# SBH_Charger_Main.net
KiCad netlist of a schematic drawn in Altium Designer
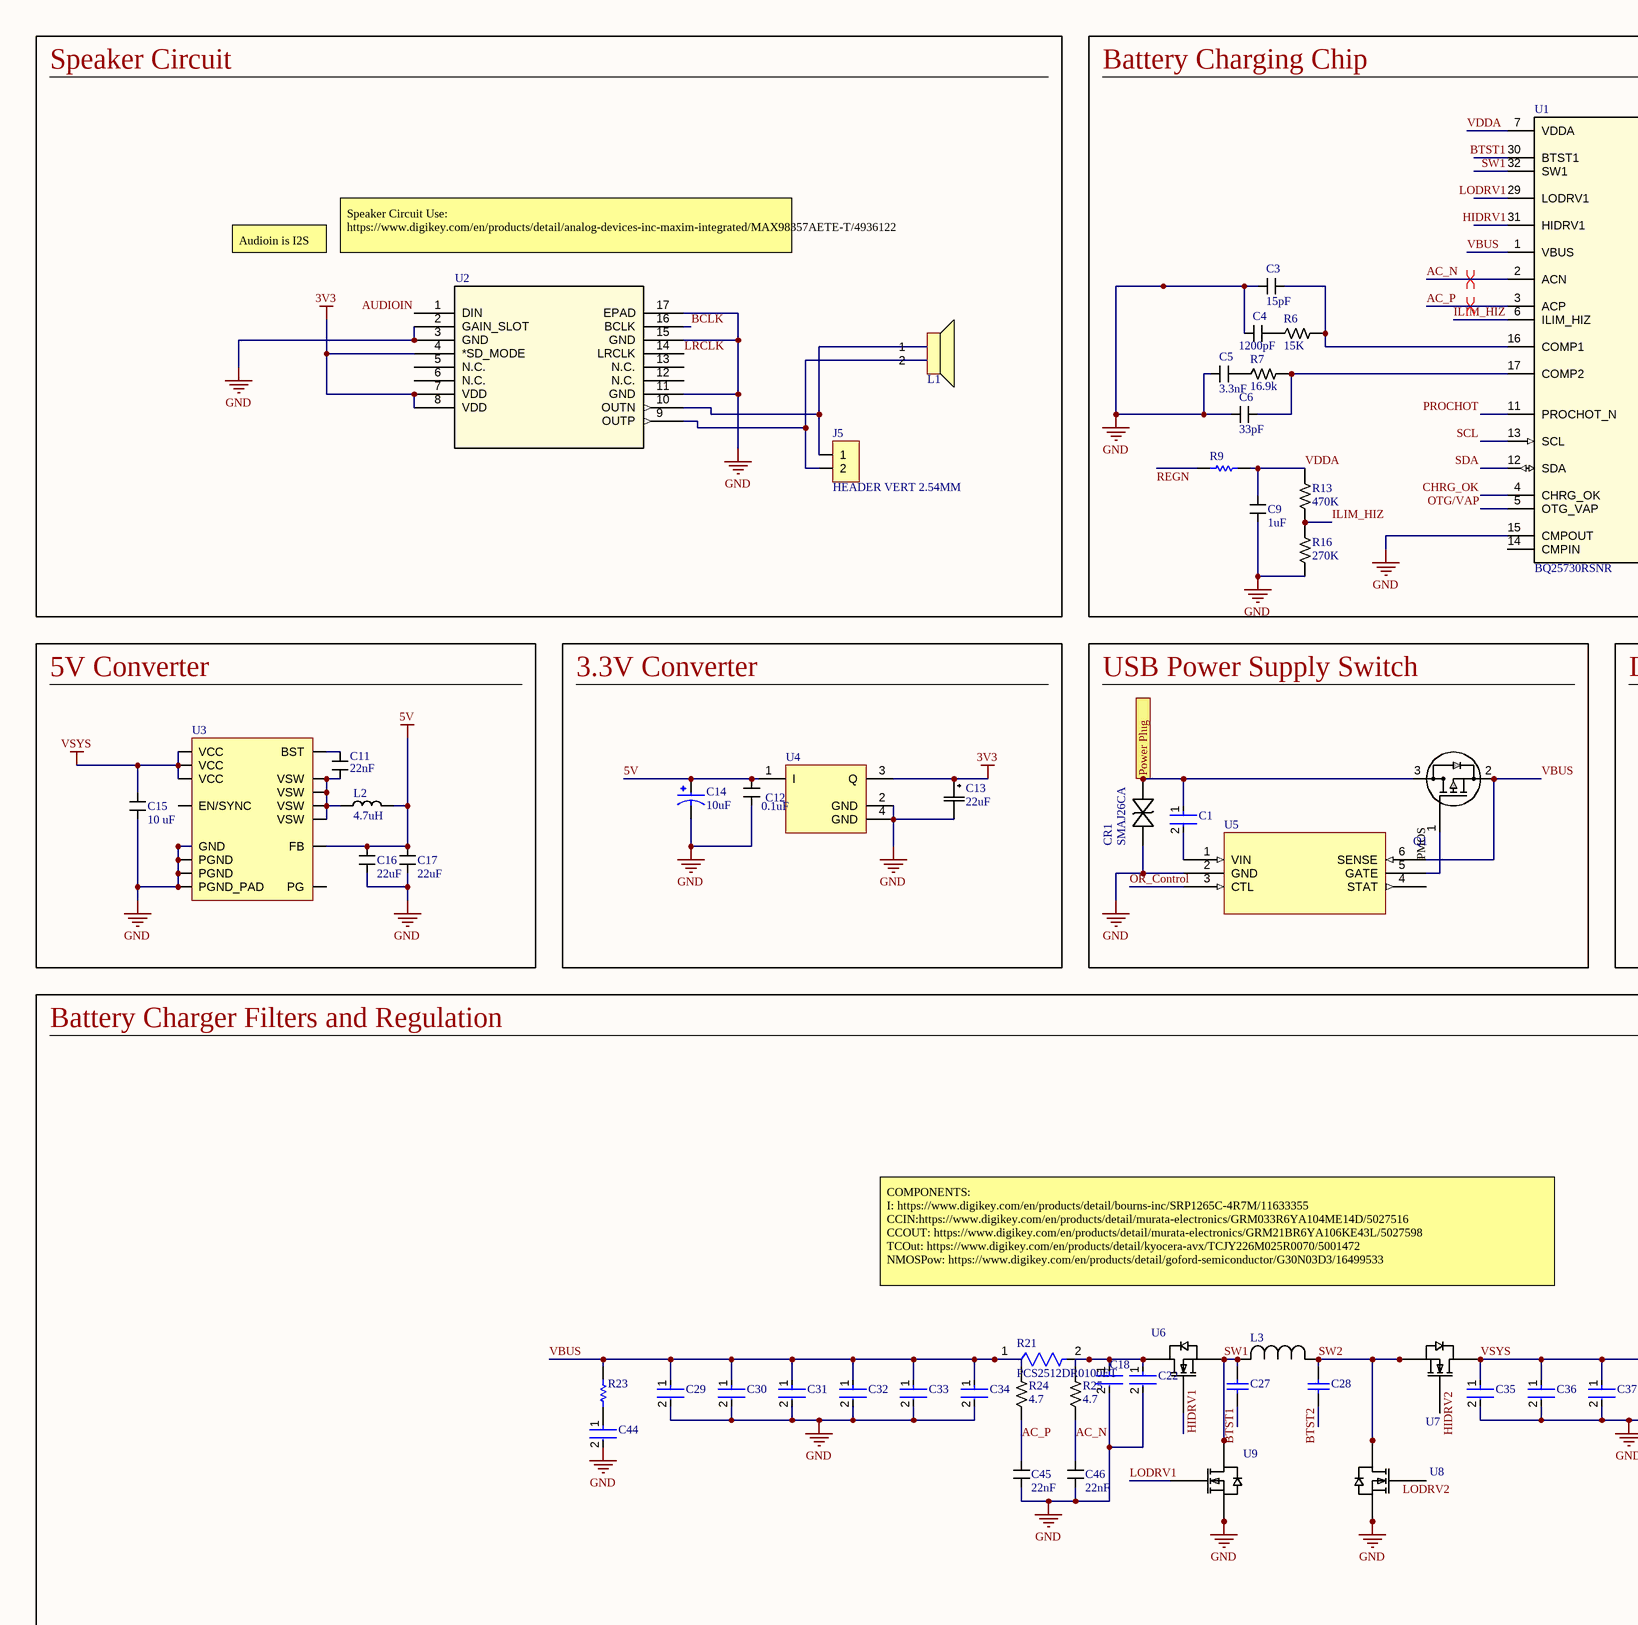
[diagram p0: SBH_Charger_Main.SchDoc, left]
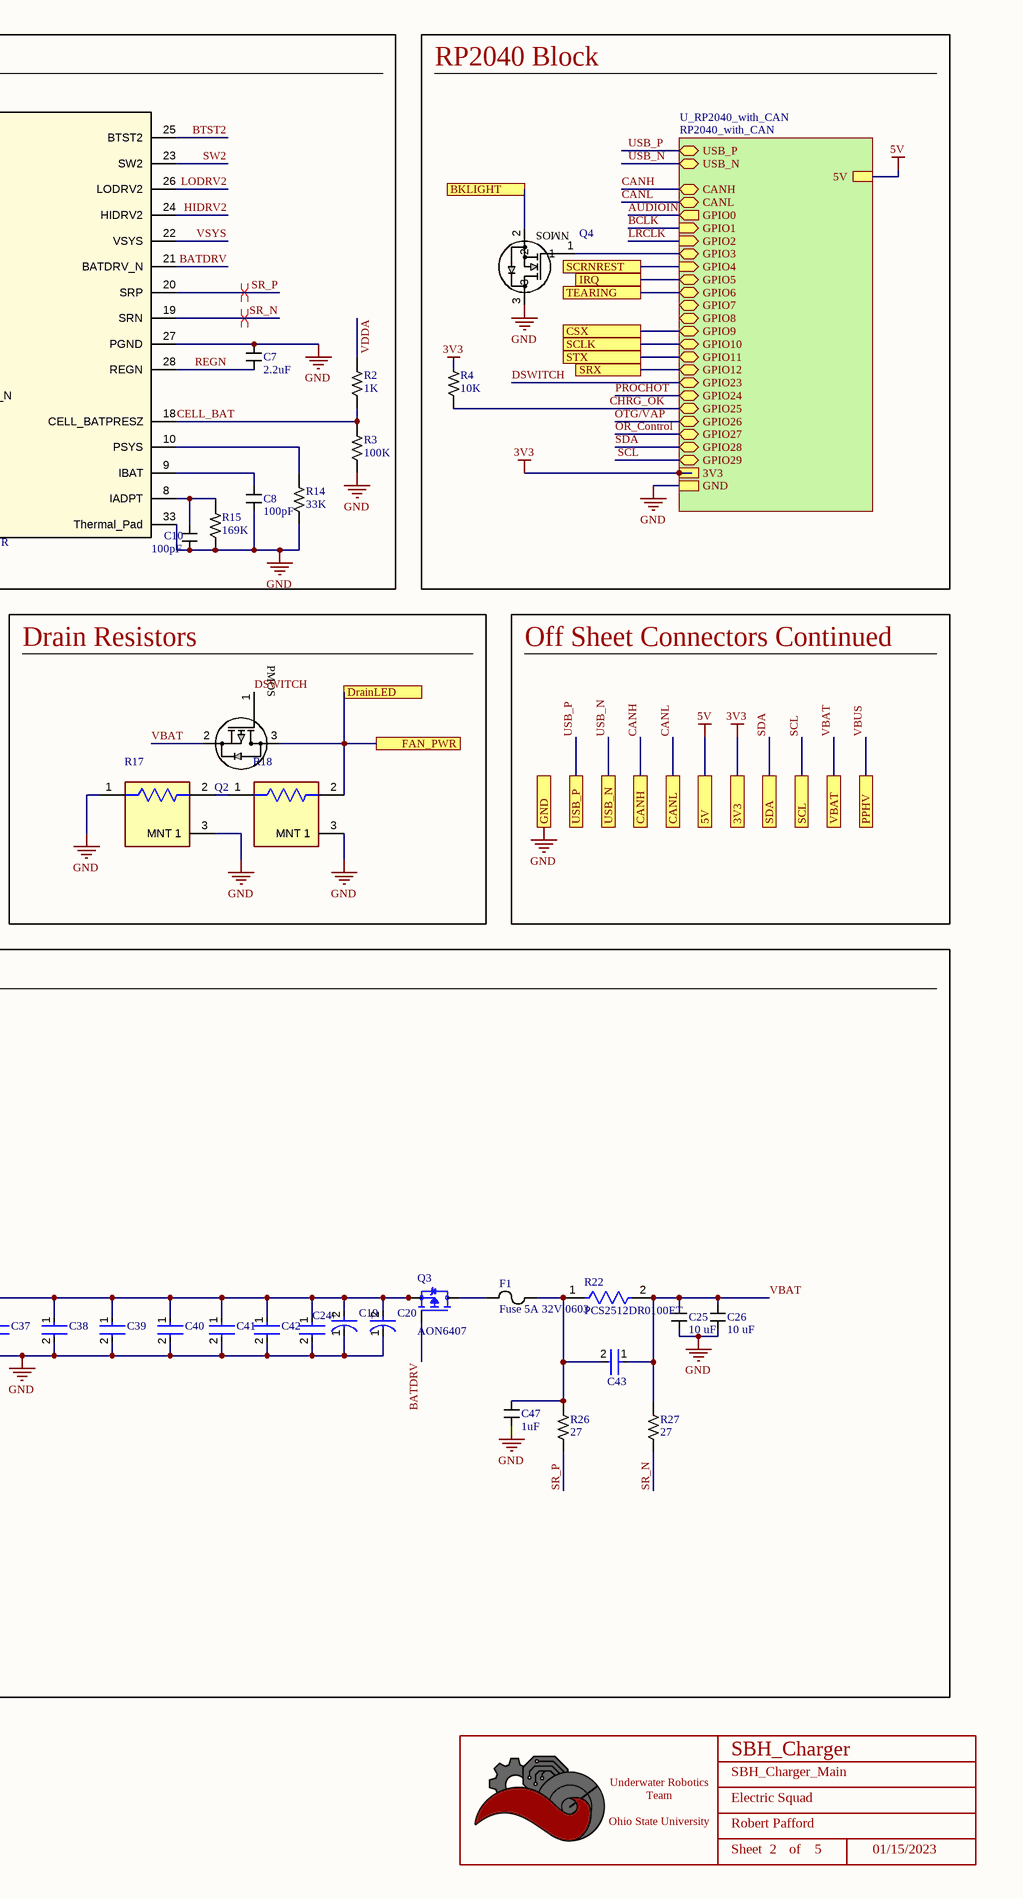
[diagram p1: SBH_Charger_Main.SchDoc, right]

(export (version "E")
  (design (tool "Eeschema 10.0.6"))
  (components
    (comp (ref "C1")
      (value "CC0402KRX7R9BB103")
      (footprint "CAPACITOR_0402")
      (description "CAP CER 10000PF 50V X7R 0402")
      (fields
        (field (name "OCTOPART") "https://octopart.com/cc0402krx7r9bb103-yageo-8376513")
        (field (name "MANUFACTURER") "YAGEO")
      )
      (libsource (lib "Capacitors") (part "CAP CER 0.01 UF 0402"))
    )
    (comp (ref "C3")
      (value "15pF")
      (footprint "CAPACITOR_0402")
      (description "CAP CER 15PF 50V C0G/NP0 0402")
      (fields
        (field (name "TOLERANCE") "+/- 5%")
        (field (name "VOLTAGE") "50V")
        (field (name "MADE BY") "Robert Pafford")
      )
      (libsource (lib "Capacitors") (part "CAPACITOR_0.000015uF_0402"))
    )
    (comp (ref "C4")
      (value "1200pF")
      (footprint "CAPACITOR_0402")
      (description "CAP CER 1200PF 50V X7R 0402")
      (fields
        (field (name "TOLERANCE") "+/- 5%")
        (field (name "VOLTAGE") "50V")
        (field (name "MADE BY") "Robert Pafford")
      )
      (libsource (lib "Capacitors") (part "CAPACITOR_0.0012uF_0402"))
    )
    (comp (ref "C5")
      (value "3.3nF")
      (footprint "CAPACITOR_0402")
      (description "CAP CER 3300PF 50V X7R 0402")
      (fields
        (field (name "TOLERANCE") "+/- 5%")
        (field (name "VOLTAGE") "50V")
        (field (name "MADE BY") "Robert Pafford")
      )
      (libsource (lib "Capacitors") (part "CAPACITOR_0.0033uF_0402"))
    )
    (comp (ref "C6")
      (value "33pF")
      (footprint "CAPACITOR_0402")
      (description "CAP CER 33PF 50V C0G/NP0 0402")
      (fields
        (field (name "TOLERANCE") "+/- 5%")
        (field (name "VOLTAGE") "50V")
        (field (name "MADE BY") "Robert Pafford")
      )
      (libsource (lib "Capacitors") (part "CAPACITOR_0.000033uF_0402"))
    )
    (comp (ref "C7")
      (value "2.2uF")
      (footprint "CAPACITOR_0402")
      (description "Cap 2.2uF 35V +/-10%\r\nCeramic 0402")
      (fields
        (field (name "TOLERANCE") "+/- 10%")
        (field (name "VOLTAGE") "35V")
        (field (name "MADE BY") "Flip B")
      )
      (libsource (lib "Capacitors") (part "CAPACITOR_2.2uF_0402"))
    )
    (comp (ref "C8")
      (value "100pF")
      (footprint "CAPACITOR_0603")
      (description "CAP CER 100PF 50V C0G/NP0 0603")
      (fields
        (field (name "TOLERANCE") "+/- 5%")
        (field (name "VOLTAGE") "50V")
        (field (name "MADE BY") "Robert Pafford")
      )
      (libsource (lib "Capacitors") (part "CAPACITOR_0.0001uF_0603"))
    )
    (comp (ref "C9")
      (value "1uF")
      (footprint "CAPACITOR_0603")
      (description "Cap 1uF 16V +/-10%\r\nCeramic 0603")
      (fields
        (field (name "TOLERANCE") "+/- 10%")
        (field (name "VOLTAGE") "16V")
        (field (name "MADE BY") "Flip B")
      )
      (libsource (lib "Capacitors") (part "CAPACITOR_1uF_0603"))
    )
    (comp (ref "C10")
      (value "100pF")
      (footprint "CAPACITOR_0603")
      (description "CAP CER 100PF 50V C0G/NP0 0603")
      (fields
        (field (name "TOLERANCE") "+/- 5%")
        (field (name "VOLTAGE") "50V")
        (field (name "MADE BY") "Robert Pafford")
      )
      (libsource (lib "Capacitors") (part "CAPACITOR_0.0001uF_0603"))
    )
    (comp (ref "C11")
      (value "22nF")
      (footprint "CAPACITOR_0402")
      (description "Cap 22nF 25V +/-10%\r\nCeramic 0402")
      (fields
        (field (name "TOLERANCE") "+/- 10%")
        (field (name "VOLTAGE") "25V")
        (field (name "MADE BY") "Robert Pafford")
      )
      (libsource (lib "Capacitors") (part "CAPACITOR_0.022uF_0402"))
    )
    (comp (ref "C12")
      (value "0.1uF")
      (footprint "CAPACITOR_0603")
      (description "Cap 100nF 25V +/-10%\r\nCeramic 0603")
      (fields
        (field (name "TOLERANCE") "+/- 10%")
        (field (name "VOLTAGE") "6.3V")
        (field (name "MADE BY") "Flip B")
      )
      (libsource (lib "Capacitors") (part "CAPACITOR_0.1uF_0603_25V"))
    )
    (comp (ref "C13")
      (value "22uF")
      (footprint "PCAP_8x5.4-ELECT_NCA")
      (description "22 µF 35 V Aluminum Electrolytic Capacitors Radial, Can - SMD 1000 Hrs")
      (fields
        (field (name "VOLTAGE") "35V")
        (field (name "Comment") "22uF electrolytic 35 V")
        (field (name "MADE BY") "Robert Pafford")
      )
      (libsource (lib "Capacitors") (part "CAP ALUM 22UF 20% 35V SMD"))
    )
    (comp (ref "C14")
      (value "10uF")
      (footprint "CAP_EEHZC1J100P")
      (description "10 µF 63 V Aluminum - Polymer Capacitors Radial, Can SMD 120mOhm")
      (fields
        (field (name "TOLERANCE") "+/- 20%")
        (field (name "Comment") "10uF electrolytic 63V")
        (field (name "MADE BY") "Robert Pafford")
      )
      (libsource (lib "Capacitors") (part "CAP ALUM 10UF 20% 63V SMD"))
    )
    (comp (ref "C15")
      (value "10uF Ceramic 25V")
      (footprint "CAPACITOR_1206")
      (description "Cap 10uF 25V +/-10%\r\nCeramic 1206")
      (fields
        (field (name "TOLERANCE") "+/- 10%")
        (field (name "VOLTAGE") "25V")
        (field (name "VALUE (UF)") "10 uF")
        (field (name "MADE BY") "Robert Pafford")
      )
      (libsource (lib "Capacitors") (part "CAPACITOR_10uF_1206"))
    )
    (comp (ref "C16")
      (value "22uF")
      (footprint "CAPACITOR_0805")
      (description "Cap 22uF 10V +/-20% X5R\r\nCeramic 0805")
      (fields
        (field (name "TOLERANCE") "+/- 20%")
        (field (name "VOLTAGE") "10V")
        (field (name "MADE BY") "Robert Pafford")
      )
      (libsource (lib "Capacitors") (part "CAPACITOR_22uF_0805"))
    )
    (comp (ref "C17")
      (value "22uF")
      (footprint "CAPACITOR_0805")
      (description "Cap 22uF 10V +/-20% X5R\r\nCeramic 0805")
      (fields
        (field (name "TOLERANCE") "+/- 20%")
        (field (name "VOLTAGE") "10V")
        (field (name "MADE BY") "Robert Pafford")
      )
      (libsource (lib "Capacitors") (part "CAPACITOR_22uF_0805"))
    )
    (comp (ref "C18")
      (value "CC0402KRX7R9BB103")
      (footprint "FP-CC0402-MFG")
      (description "CAP CER 10000PF 50V X7R 0402")
      (fields
        (field (name "OCTOPART") "https://octopart.com/cc0402krx7r9bb103-yageo-8376513")
        (field (name "MANUFACTURER") "YAGEO")
      )
      (libsource (lib "Altium Content Vault") (part "11868f565c42a9108669ba33697ecf6"))
    )
    (comp (ref "C19")
      (value "TAJD226K035RNJ")
      (footprint "FP-TAJD-MFG")
      (description "22uF 35V  ±10% 900mΩ 2917  SMD Tantalum Capacitor")
      (fields (field (name "TOLERANCE") "10%") (field (name "VOLTAGE") "35V"))
      (libsource (lib "Altium Content Vault") (part "a00bbbee19879c290e62620ae7e47b1"))
    )
    (comp (ref "C20")
      (value "TAJD226K035RNJ")
      (footprint "FP-TAJD-MFG")
      (description "22uF 35V  ±10% 900mΩ 2917  SMD Tantalum Capacitor")
      (fields (field (name "TOLERANCE") "10%") (field (name "VOLTAGE") "35V"))
      (libsource (lib "Altium Content Vault") (part "a00bbbee19879c290e62620ae7e47b1"))
    )
    (comp (ref "C22")
      (value "C0402C102J5GACTU")
      (footprint "FP-C0402-BB-MFG")
      (description "CAP CER 1000PF 50V 5% NP0 0402")
      (fields
        (field (name "OCTOPART") "https://octopart.com/c0402c102j5gactu-kemet-9145103")
        (field (name "TOLERANCE") "0.05")
      )
      (libsource (lib "Altium Content Vault") (part "b4654b650e69147ec39a6b967a45e02"))
    )
    (comp (ref "C24")
      (value "C3216X7R1V106M160AC")
      (footprint "FP-C3216-160-0_2-IPC_C")
      (description "Multilayer Ceramic Capacitors 10uF ±20% 35V X7R SMD 1206")
      (fields (field (name "TOLERANCE") "20%"))
      (libsource (lib "Altium Content Vault") (part "11868f565c42a9108669ba33697ecf6"))
    )
    (comp (ref "C25")
      (value "10uF Ceramic 25V")
      (footprint "CAPACITOR_1206")
      (description "Cap 10uF 25V +/-10%\r\nCeramic 1206")
      (fields
        (field (name "TOLERANCE") "+/- 10%")
        (field (name "VOLTAGE") "25V")
        (field (name "VALUE (UF)") "10 uF")
        (field (name "MADE BY") "Robert Pafford")
      )
      (libsource (lib "Capacitors") (part "CAPACITOR_10uF_1206"))
    )
    (comp (ref "C26")
      (value "10uF Ceramic 25V")
      (footprint "CAPACITOR_1206")
      (description "Cap 10uF 25V +/-10%\r\nCeramic 1206")
      (fields
        (field (name "TOLERANCE") "+/- 10%")
        (field (name "VOLTAGE") "25V")
        (field (name "VALUE (UF)") "10 uF")
        (field (name "MADE BY") "Robert Pafford")
      )
      (libsource (lib "Capacitors") (part "CAPACITOR_10uF_1206"))
    )
    (comp (ref "C27")
      (value "GRM188R71H473KA61D")
      (footprint "CAPC1608X90X35ML10T15")
      (fields (field (name "MANUFACTURER") "Murata"))
      (libsource (lib "Altium Content Vault") (part "CAP"))
    )
    (comp (ref "C28")
      (value "GRM188R71H473KA61D")
      (footprint "CAPC1608X90X35ML10T15")
      (fields (field (name "MANUFACTURER") "Murata"))
      (libsource (lib "Altium Content Vault") (part "CAP"))
    )
    (comp (ref "C29")
      (value "C3216X7R1V106M160AC")
      (footprint "FP-C3216-160-0_2-IPC_C")
      (description "Multilayer Ceramic Capacitors 10uF ±20% 35V X7R SMD 1206")
      (fields (field (name "TOLERANCE") "20%"))
      (libsource (lib "Altium Content Vault") (part "11868f565c42a9108669ba33697ecf6"))
    )
    (comp (ref "C30")
      (value "C3216X7R1V106M160AC")
      (footprint "FP-C3216-160-0_2-IPC_C")
      (description "Multilayer Ceramic Capacitors 10uF ±20% 35V X7R SMD 1206")
      (fields (field (name "TOLERANCE") "20%"))
      (libsource (lib "Altium Content Vault") (part "11868f565c42a9108669ba33697ecf6"))
    )
    (comp (ref "C31")
      (value "C3216X7R1V106M160AC")
      (footprint "FP-C3216-160-0_2-IPC_C")
      (description "Multilayer Ceramic Capacitors 10uF ±20% 35V X7R SMD 1206")
      (fields (field (name "TOLERANCE") "20%"))
      (libsource (lib "Altium Content Vault") (part "11868f565c42a9108669ba33697ecf6"))
    )
    (comp (ref "C32")
      (value "C3216X7R1V106M160AC")
      (footprint "FP-C3216-160-0_2-IPC_C")
      (description "Multilayer Ceramic Capacitors 10uF ±20% 35V X7R SMD 1206")
      (fields (field (name "TOLERANCE") "20%"))
      (libsource (lib "Altium Content Vault") (part "11868f565c42a9108669ba33697ecf6"))
    )
    (comp (ref "C33")
      (value "C3216X7R1V106M160AC")
      (footprint "FP-C3216-160-0_2-IPC_C")
      (description "Multilayer Ceramic Capacitors 10uF ±20% 35V X7R SMD 1206")
      (fields (field (name "TOLERANCE") "20%"))
      (libsource (lib "Altium Content Vault") (part "11868f565c42a9108669ba33697ecf6"))
    )
    (comp (ref "C34")
      (value "C3216X7R1V106M160AC")
      (footprint "FP-C3216-160-0_2-IPC_C")
      (description "Multilayer Ceramic Capacitors 10uF ±20% 35V X7R SMD 1206")
      (fields (field (name "TOLERANCE") "20%"))
      (libsource (lib "Altium Content Vault") (part "11868f565c42a9108669ba33697ecf6"))
    )
    (comp (ref "C35")
      (value "C3216X7R1V106M160AC")
      (footprint "FP-C3216-160-0_2-IPC_C")
      (description "Multilayer Ceramic Capacitors 10uF ±20% 35V X7R SMD 1206")
      (fields (field (name "TOLERANCE") "20%"))
      (libsource (lib "Altium Content Vault") (part "11868f565c42a9108669ba33697ecf6"))
    )
    (comp (ref "C36")
      (value "C3216X7R1V106M160AC")
      (footprint "FP-C3216-160-0_2-IPC_C")
      (description "Multilayer Ceramic Capacitors 10uF ±20% 35V X7R SMD 1206")
      (fields (field (name "TOLERANCE") "20%"))
      (libsource (lib "Altium Content Vault") (part "11868f565c42a9108669ba33697ecf6"))
    )
    (comp (ref "C37")
      (value "C3216X7R1V106M160AC")
      (footprint "FP-C3216-160-0_2-IPC_C")
      (description "Multilayer Ceramic Capacitors 10uF ±20% 35V X7R SMD 1206")
      (fields (field (name "TOLERANCE") "20%"))
      (libsource (lib "Altium Content Vault") (part "11868f565c42a9108669ba33697ecf6"))
    )
    (comp (ref "C38")
      (value "C3216X7R1V106M160AC")
      (footprint "FP-C3216-160-0_2-IPC_C")
      (description "Multilayer Ceramic Capacitors 10uF ±20% 35V X7R SMD 1206")
      (fields (field (name "TOLERANCE") "20%"))
      (libsource (lib "Altium Content Vault") (part "11868f565c42a9108669ba33697ecf6"))
    )
    (comp (ref "C39")
      (value "C3216X7R1V106M160AC")
      (footprint "FP-C3216-160-0_2-IPC_C")
      (description "Multilayer Ceramic Capacitors 10uF ±20% 35V X7R SMD 1206")
      (fields (field (name "TOLERANCE") "20%"))
      (libsource (lib "Altium Content Vault") (part "11868f565c42a9108669ba33697ecf6"))
    )
    (comp (ref "C40")
      (value "C3216X7R1V106M160AC")
      (footprint "FP-C3216-160-0_2-IPC_C")
      (description "Multilayer Ceramic Capacitors 10uF ±20% 35V X7R SMD 1206")
      (fields (field (name "TOLERANCE") "20%"))
      (libsource (lib "Altium Content Vault") (part "11868f565c42a9108669ba33697ecf6"))
    )
    (comp (ref "C41")
      (value "C3216X7R1V106M160AC")
      (footprint "FP-C3216-160-0_2-IPC_C")
      (description "Multilayer Ceramic Capacitors 10uF ±20% 35V X7R SMD 1206")
      (fields (field (name "TOLERANCE") "20%"))
      (libsource (lib "Altium Content Vault") (part "11868f565c42a9108669ba33697ecf6"))
    )
    (comp (ref "C42")
      (value "C3216X7R1V106M160AC")
      (footprint "FP-C3216-160-0_2-IPC_C")
      (description "Multilayer Ceramic Capacitors 10uF ±20% 35V X7R SMD 1206")
      (fields (field (name "TOLERANCE") "20%"))
      (libsource (lib "Altium Content Vault") (part "11868f565c42a9108669ba33697ecf6"))
    )
    (comp (ref "C43")
      (value "GRM033R6YA104ME14D")
      (footprint "FP-GRM033-0_03-IPC_C")
      (description "Chip Multilayer Ceramic Capacitors for General Purpose, 0201, 0.10uF, X5R, 15%, 20%, 35V")
      (fields (field (name "TOLERANCE") "20%"))
      (libsource (lib "Capacitors") (part "CAPACITOR_0.1uF_0603_1"))
    )
    (comp (ref "C44")
      (value "UMK107AB7105KA-T")
      (footprint "FP-0603-L_1_6_0_15-W_0_8-IPC_C")
      (description "Ceramic Capacitor General Use 1uF ±10% 50V X7R 0603")
      (fields (field (name "TOLERANCE") "10%"))
      (libsource (lib "Altium Content Vault") (part "11868f565c42a9108669ba33697ecf6"))
    )
    (comp (ref "C45")
      (value "22nF")
      (footprint "CAPACITOR_0402")
      (description "Cap 22nF 25V +/-10%\r\nCeramic 0402")
      (fields
        (field (name "TOLERANCE") "+/- 10%")
        (field (name "VOLTAGE") "25V")
        (field (name "MADE BY") "Robert Pafford")
      )
      (libsource (lib "Capacitors") (part "CAPACITOR_0.022uF_0402"))
    )
    (comp (ref "C46")
      (value "22nF")
      (footprint "CAPACITOR_0402")
      (description "Cap 22nF 25V +/-10%\r\nCeramic 0402")
      (fields
        (field (name "TOLERANCE") "+/- 10%")
        (field (name "VOLTAGE") "25V")
        (field (name "MADE BY") "Robert Pafford")
      )
      (libsource (lib "Capacitors") (part "CAPACITOR_0.022uF_0402"))
    )
    (comp (ref "C47")
      (value "1uF")
      (footprint "CAPACITOR_0603")
      (description "Cap 1uF 16V +/-10%\r\nCeramic 0603")
      (fields
        (field (name "TOLERANCE") "+/- 10%")
        (field (name "VOLTAGE") "16V")
        (field (name "MADE BY") "Flip B")
      )
      (libsource (lib "Capacitors") (part "CAPACITOR_1uF_0603"))
    )
    (comp (ref "CR1")
      (value "SMAJ26CA")
      (footprint "SMASeries_LTF")
      (description "TVS DIODE 26VWM 42.1VC DO214AC")
      (fields (field (name "COPYRIGHT") "Copyright (C) 2024 Ultra Librarian. All rights reserved."))
      (libsource (lib "Diodes") (part "TVS_SMAJ26CA"))
    )
    (comp (ref "F1")
      (value "Fuse 5A 32V 0603")
      (footprint "2-SMD Fuse 0603")
      (description "Pansonic ¦ 32V ¦ 5A ¦ 0603 ¦ Fast Blow")
      (fields
        (field (name "MANUFACTURER_PART_NUMBER") "ERB-RE5R00V")
        (field (name "CREATED BY") "Robert Pafford")
      )
      (libsource (lib "Fuses") (part "ERB-RE5R00V"))
    )
    (comp (ref "J5")
      (value "HEADER VERT 2.54MM")
      (footprint "HEADER_2PIN_2.54MM")
      (description "CONN HEADER VERT 2POS 2.54MM")
      (fields (field (name "CREATED BY") "Robert P"))
      (libsource (lib "Connectors") (part "HEADER_2PIN_2.54MM"))
    )
    (comp (ref "L1")
      (value "SPEAKER_SP_1609S")
      (footprint "SPEAKER_SP-1609S")
      (description "8 Ohms General Purpose Speaker 700 mW 200 Hz ~ 5 kHz Top Rectangular")
      (libsource (lib "Inductors") (part "SPEAKER_SP_1609S"))
    )
    (comp (ref "L2")
      (value "4.7uH")
      (footprint "INDUCTOR_SLF7045")
      (description "4.7 µH Shielded Drum Core, Wirewound Inductor 2.1 A 36mOhm Max Nonstandard")
      (fields
        (field (name "TOLERANCE") "+/- 20%")
        (field (name "Comment") "4.7uH Shielded Drum Core")
        (field (name "MADE BY") "Robert Pafford")
      )
      (libsource (lib "Inductors") (part "INDUCTOR_4.7uH_SLF7045T"))
    )
    (comp (ref "L3")
      (value "SRP1770TA-3R3M")
      (footprint "INDUCTOR_SRP1770TA-3R3M_BRN")
      (description "3.3 µH Shielded Drum Core, Wirewound Inductor 28 A 3.9mOhm Max Nonstandard")
      (fields
        (field (name "MANUFACTURER_PART_NUMBER") "SRP1265C-4R7M")
        (field (name "COPYRIGHT") "Copyright (C) 2023 Ultra Librarian. All rights reserved.")
      )
      (libsource (lib "Inductors") (part "INDUCTOR_3.3uH_SRP1770TA_3R3M"))
    )
    (comp (ref "Q1")
      (value "DMP3056L-7")
      (footprint "SOT-23-3")
      (description "P-Channel 30V 4.3A (Ta) 1.38W (Ta) Surface Mount SOT23")
      (fields (field (name "CREATED BY") "John Ulm") (field (name "REVIEWED BY") "---"))
      (libsource (lib "Transistors") (part "DMP3056L-7"))
    )
    (comp (ref "Q2")
      (value "DMP3056L-7")
      (footprint "SOT-23-3")
      (description "P-Channel 30V 4.3A (Ta) 1.38W (Ta) Surface Mount SOT23")
      (fields (field (name "CREATED BY") "John Ulm") (field (name "REVIEWED BY") "---"))
      (libsource (lib "Transistors") (part "DMP3056L-7"))
    )
    (comp (ref "Q3")
      (value "AON6407")
      (footprint "TRANS_AON6407")
      (description "P-Channel 30V 32A (Ta), 85A (Tc) 7.3W (Ta), 83W (Tc) Surface Mount 8-DFN (5x6)")
      (fields (field (name "DIGI-KEY_PART_NUMBER") "785-1421-1-ND") (field (name "MF") "Alpha &"))
      (libsource (lib "Transistors") (part "AON6407"))
    )
    (comp (ref "Q4")
      (value "MOSFET N-CH 30V 5.8A SOT-23-3")
      (footprint "SOT-23-3")
      (description "N-Channel 30 V 5.8A (Ta) 1.4W (Ta) Surface Mount SOT-23-3")
      (fields (field (name "MANUFACTURER _PART_NUMBER") "AO3404A") (field (name "CREATED BY") "Dylan T"))
      (libsource (lib "Transistors") (part "AO3404A"))
    )
    (comp (ref "R2")
      (value "1k Ohm 5% 1/8W")
      (footprint "RESISTOR_0603")
      (description "RES 1k OHM 5% 1/8W 0603")
      (fields
        (field (name "TOLERANCE") "+/- 5%")
        (field (name "VALUE  (OHMS)") "1K")
        (field (name "MADE BY") "Robert Pafford")
      )
      (libsource (lib "Resistors") (part "RESISTOR_1K_0603"))
    )
    (comp (ref "R3")
      (value "100k Ohm 5% 1/8W")
      (footprint "RESISTOR_0603")
      (description "RES 100k OHM 5% 1/10W 0603")
      (fields
        (field (name "TOLERANCE") "+/- 5%")
        (field (name "VALUE  (OHMS)") "100K")
        (field (name "MADE BY") "Flip B")
      )
      (libsource (lib "Resistors") (part "RESISTOR_100K_0603"))
    )
    (comp (ref "R4")
      (value "10k Ohm 5% 1/10W")
      (footprint "RESISTOR_0603")
      (description "RES 10k OHM 5% 1/10W 0603")
      (fields
        (field (name "TOLERANCE") "+/- 5%")
        (field (name "VALUE  (OHMS)") "10K")
        (field (name "MADE BY") "Robert Pafford")
      )
      (libsource (lib "Resistors") (part "RESISTOR_10K_0603"))
    )
    (comp (ref "R6")
      (value "15k Ohm 5% 1/10W")
      (footprint "RESISTOR_0603")
      (description "RES 15k OHM 5% 1/10W 0603")
      (fields
        (field (name "TOLERANCE") "+/- 5%")
        (field (name "VALUE  (OHMS)") "15K")
        (field (name "MADE BY") "Dylan Trainor")
      )
      (libsource (lib "Resistors") (part "RESISTOR_15K_0603"))
    )
    (comp (ref "R7")
      (value "16.9k Ohm 1% 1/16W")
      (footprint "RESISTOR_0402")
      (description "16.9 kOhms ±1% 0.063W, 1/16W Chip Resistor 0402 (1005 Metric) Moisture Resistant Thick Film")
      (fields
        (field (name "TOLERANCE") "+/- 1%")
        (field (name "VALUE  (OHMS)") "16.9k")
        (field (name "MADE BY") "Andrew Lin")
      )
      (libsource (lib "Resistors") (part "RESISTOR_16.9K_0402"))
    )
    (comp (ref "R9")
      (value "CRCW040210R0FKEDHP")
      (footprint "RESC1005X40X25NL05T10")
      (fields (field (name "MANUFACTURER") "Vishay Dale"))
      (libsource (lib "Altium Content Vault") (part "RES"))
    )
    (comp (ref "R13")
      (value "470k Ohm 5% 1/10W")
      (footprint "RESISTOR_0603")
      (description "RES 470k OHM 5% 1/10W 0603")
      (fields
        (field (name "TOLERANCE") "+/- 5%")
        (field (name "VALUE  (OHMS)") "470K")
        (field (name "MADE BY") "Robert P")
      )
      (libsource (lib "Resistors") (part "RESISTOR_470K_0603"))
    )
    (comp (ref "R14")
      (value "33k Ohm 5% 1/8W")
      (footprint "RESISTOR_0805")
      (description "RES 33k OHM 5% 1/8W 0805")
      (fields
        (field (name "TOLERANCE") "+/- 5%")
        (field (name "VALUE  (OHMS)") "33K")
        (field (name "MADE BY") "Dylan Trainor")
      )
      (libsource (lib "Resistors") (part "RESISTOR_33K_0805"))
    )
    (comp (ref "R15")
      (value "169K OHM 1% 1/3W")
      (footprint "RESISTOR_0603")
      (fields
        (field (name "TOLERANCE") "+/- 1%")
        (field (name "VALUE  (OHMS)") "169K")
        (field (name "MADE BY") "Andrew Lin")
      )
      (libsource (lib "Resistors") (part "RESISTOR_169K_1%_0603"))
    )
    (comp (ref "R16")
      (value "270k Ohm 1% 1/10W")
      (footprint "RESISTOR_0603")
      (description "RES 270k OHM 1% 1/10W 0603")
      (fields
        (field (name "TOLERANCE") "+/- 1%")
        (field (name "VALUE  (OHMS)") "270K")
        (field (name "MADE BY") "Andrew Lin")
      )
      (libsource (lib "Resistors") (part "RESISTOR_270K_1%_0603"))
    )
    (comp (ref "R17")
      (value "PWR163S-25-10R0JE")
      (footprint "FP-PWR163-MFG")
      (description "RES SMD 10 OHM 5% 25W DPAK")
      (fields (field (name "COPYRIGHT") "Copyright (C) 2023 Ultra Librarian. All rights reserved."))
      (libsource (lib "Resistors") (part "PWR163S-25-10R0JE"))
    )
    (comp (ref "R18")
      (value "PWR163S-25-10R0JE")
      (footprint "FP-PWR163-MFG")
      (description "RES SMD 10 OHM 5% 25W DPAK")
      (fields (field (name "COPYRIGHT") "Copyright (C) 2023 Ultra Librarian. All rights reserved."))
      (libsource (lib "Resistors") (part "PWR163S-25-10R0JE"))
    )
    (comp (ref "R21")
      (value "PCS2512DR0100ET")
      (footprint "FP-PCS2512-MFG")
      (description "2W 0.010 OHMS 0.5% 2512")
      (fields
        (field (name "OCTOPART") "https://octopart.com/pcs2512dr0100et-ohmite-106082038")
        (field (name "TOLERANCE") "0.%")
      )
      (libsource (lib "Altium Content Vault") (part "1029c3af85768c4190bb7ad29bc67b5"))
    )
    (comp (ref "R22")
      (value "PCS2512DR0100ET")
      (footprint "FP-PCS2512-MFG")
      (description "2W 0.010 OHMS 0.5% 2512")
      (fields
        (field (name "OCTOPART") "https://octopart.com/pcs2512dr0100et-ohmite-106082038")
        (field (name "TOLERANCE") "0.%")
      )
      (libsource (lib "Altium Content Vault") (part "1029c3af85768c4190bb7ad29bc67b5"))
    )
    (comp (ref "R23")
      (value "CRCW06032R20FKEA")
      (footprint "RESC1609X50X30ML10T20")
      (fields (field (name "MANUFACTURER") "Vishay Dale"))
      (libsource (lib "Altium Content Vault") (part "RES"))
    )
    (comp (ref "R24")
      (value "4.7 Ohm 5% 1/8W")
      (footprint "RESISTOR_0603")
      (description "RES 4.7 OHM 5% 1/8W 0603")
      (fields
        (field (name "TOLERANCE") "+/- 5%")
        (field (name "VALUE  (OHMS)") "4.7")
        (field (name "MADE BY") "Robert Pafford")
      )
      (libsource (lib "Resistors") (part "RESISTOR_4.7_0603"))
    )
    (comp (ref "R25")
      (value "4.7 Ohm 5% 1/8W")
      (footprint "RESISTOR_0603")
      (description "RES 4.7 OHM 5% 1/8W 0603")
      (fields
        (field (name "TOLERANCE") "+/- 5%")
        (field (name "VALUE  (OHMS)") "4.7")
        (field (name "MADE BY") "Robert Pafford")
      )
      (libsource (lib "Resistors") (part "RESISTOR_4.7_0603"))
    )
    (comp (ref "R26")
      (value "27 Ohm 5% 1/8W")
      (footprint "RESISTOR_0603")
      (description "RES 27 OHM 5% 1/8W 0603")
      (fields
        (field (name "TOLERANCE") "+/- 5%")
        (field (name "VALUE  (OHMS)") "27")
        (field (name "MADE BY") "Robert Pafford")
      )
      (libsource (lib "Resistors") (part "RESISTOR_27_0603"))
    )
    (comp (ref "R27")
      (value "27 Ohm 5% 1/8W")
      (footprint "RESISTOR_0603")
      (description "RES 27 OHM 5% 1/8W 0603")
      (fields
        (field (name "TOLERANCE") "+/- 5%")
        (field (name "VALUE  (OHMS)") "27")
        (field (name "MADE BY") "Robert Pafford")
      )
      (libsource (lib "Resistors") (part "RESISTOR_27_0603"))
    )
    (comp (ref "U1")
      (value "BQ25730RSNR")
      (footprint "RSN0032B-IPC_B")
      (description "I2C 1 TO 5 CELL, 2-V, NARROW VDC, Charger IC Multi-Chemistry 32-QFN (4x4)")
      (fields (field (name "COPYRIGHT") "Copyright (C) 2024 Ultra Librarian. All rights reserved."))
      (libsource (lib "Integrated Circuits") (part "BQ25730RSNR"))
    )
    (comp (ref "U2")
      (value "MAX98357AETE+T")
      (footprint "TQFN-16")
      (description "Audio Amplifiers Digital Input Class D Amplifier")
      (fields (field (name "MADE BY") "Andrew Lin"))
      (libsource (lib "Integrated Circuits") (part "MAX98357AETE+T"))
    )
    (comp (ref "U3")
      (value "REG BUCK 5V 1A")
      (footprint "QFN-16 (3x3)")
      (description "Buck Switching Regulator IC Positive Fixed 5V 1 Output 1A 16-VFQFN Exposed Pad")
      (fields (field (name "MADE BY") "Robert Pafford"))
      (libsource (lib "Integrated Circuits") (part "TS30041-M050QFNR"))
    )
    (comp (ref "U4")
      (value "TLE42744GS V33")
      (footprint "INF-PG-SOT223_SC-73_N")
      (fields (field (name "MANUFACTURER") "Infineon"))
      (libsource (lib "Integrated Circuits") (part "CMP-1109-00085-1"))
    )
    (comp (ref "U5")
      (value "LTC4412ES6TRPBF")
      (footprint "TSOT-23_S6")
      (description "OR Controller Source Selector Switch P-Channel 2:1 TSOT-23-6")
      (fields (field (name "MP") "LTC4412ES6#TRPBF") (field (name "MF") "Analog Devices"))
      (libsource (lib "Integrated Circuits") (part "LTC4412ES6TRPBF"))
    )
    (comp (ref "U6")
      (value "G30N03D3")
      (footprint "DNH0008A_NV")
      (description "N-Channel 30 V 30A 24W Surface Mount 8-DFN (3.15x3.05)")
      (fields (field (name "COPYRIGHT") "Copyright (C) 2023 Ultra Librarian. All rights reserved."))
      (libsource (lib "Transistors") (part "G30N03D3"))
    )
    (comp (ref "U7")
      (value "G30N03D3")
      (footprint "DNH0008A_NV")
      (description "N-Channel 30 V 30A 24W Surface Mount 8-DFN (3.15x3.05)")
      (fields (field (name "COPYRIGHT") "Copyright (C) 2023 Ultra Librarian. All rights reserved."))
      (libsource (lib "Transistors") (part "G30N03D3"))
    )
    (comp (ref "U8")
      (value "G30N03D3")
      (footprint "DNH0008A_NV")
      (description "N-Channel 30 V 30A 24W Surface Mount 8-DFN (3.15x3.05)")
      (fields (field (name "COPYRIGHT") "Copyright (C) 2023 Ultra Librarian. All rights reserved."))
      (libsource (lib "Transistors") (part "G30N03D3"))
    )
    (comp (ref "U9")
      (value "G30N03D3")
      (footprint "DNH0008A_NV")
      (description "N-Channel 30 V 30A 24W Surface Mount 8-DFN (3.15x3.05)")
      (fields (field (name "COPYRIGHT") "Copyright (C) 2023 Ultra Librarian. All rights reserved."))
      (libsource (lib "Transistors") (part "G30N03D3"))
    )
  )
  (nets
    (net (code "2") (name "/AC_N") (class "Default")
      (node (ref "C46") (pin "1") (pinfunction "1_1") (pintype "passive"))
      (node (ref "R25") (pin "2") (pinfunction "2_2") (pintype "passive"))
      (node (ref "U1") (pin "2") (pinfunction "ACN_2") (pintype "passive"))
    )
    (net (code "3") (name "/AC_P") (class "Default")
      (node (ref "C45") (pin "1") (pinfunction "1_1") (pintype "passive"))
      (node (ref "R24") (pin "2") (pinfunction "2_2") (pintype "passive"))
      (node (ref "U1") (pin "3") (pinfunction "ACP_3") (pintype "passive"))
    )
    (net (code "4") (name "/AUDIOIN") (class "Default")
      (node (ref "U2") (pin "1") (pinfunction "DIN_1") (pintype "passive"))
    )
    (net (code "5") (name "/BATDRV") (class "Default")
      (node (ref "Q3") (pin "4") (pinfunction "G_4") (pintype "passive"))
      (node (ref "U1") (pin "21") (pinfunction "BATDRV_N_21") (pintype "passive"))
    )
    (net (code "6") (name "/BCLK") (class "Default")
      (node (ref "U2") (pin "16") (pinfunction "BCLK_16") (pintype "passive"))
    )
    (net (code "7") (name "/BKLIGHT") (class "Default")
      (node (ref "Q4") (pin "2") (pinfunction "2_2") (pintype "passive"))
    )
    (net (code "8") (name "/BTST1") (class "Default")
      (node (ref "C27") (pin "1") (pinfunction "1_1") (pintype "passive"))
      (node (ref "U1") (pin "30") (pinfunction "BTST1_30") (pintype "passive"))
    )
    (net (code "9") (name "/BTST2") (class "Default")
      (node (ref "C28") (pin "1") (pinfunction "1_1") (pintype "passive"))
      (node (ref "U1") (pin "25") (pinfunction "BTST2_25") (pintype "passive"))
    )
    (net (code "12") (name "/CELL_BAT") (class "Default")
      (node (ref "R2") (pin "2") (pinfunction "2_2") (pintype "passive"))
      (node (ref "R3") (pin "1") (pinfunction "1_1") (pintype "passive"))
      (node (ref "U1") (pin "18") (pinfunction "CELL_BATPRESZ_18") (pintype "passive"))
    )
    (net (code "13") (name "/CHRG_OK") (class "Default")
      (node (ref "R4") (pin "2") (pinfunction "2_2") (pintype "passive"))
      (node (ref "U1") (pin "4") (pinfunction "CHRG_OK_4") (pintype "passive"))
    )
    (net (code "15") (name "/DSWITCH") (class "Default")
      (node (ref "Q2") (pin "1") (pinfunction "1_1") (pintype "passive"))
    )
    (net (code "16") (name "/DrainLED") (class "Default")
      (node (ref "Q2") (pin "3") (pinfunction "3_3") (pintype "passive"))
      (node (ref "R18") (pin "2") (pinfunction "2_2") (pintype "passive"))
    )
    (net (code "17") (name "/GPIO3") (class "Default")
      (node (ref "Q4") (pin "1") (pinfunction "1_1") (pintype "passive"))
    )
    (net (code "20") (name "/HIDRV1") (class "Default")
      (node (ref "U1") (pin "31") (pinfunction "HIDRV1_31") (pintype "passive"))
      (node (ref "U6") (pin "4") (pinfunction "G_4") (pintype "passive"))
    )
    (net (code "21") (name "/HIDRV2") (class "Default")
      (node (ref "U1") (pin "24") (pinfunction "HIDRV2_24") (pintype "passive"))
      (node (ref "U7") (pin "4") (pinfunction "G_4") (pintype "passive"))
    )
    (net (code "22") (name "/ILIM_HIZ") (class "Default")
      (node (ref "R13") (pin "2") (pinfunction "2_2") (pintype "passive"))
      (node (ref "R16") (pin "1") (pinfunction "1_1") (pintype "passive"))
      (node (ref "U1") (pin "6") (pinfunction "ILIM_HIZ_6") (pintype "passive"))
    )
    (net (code "24") (name "/LODRV1") (class "Default")
      (node (ref "U1") (pin "29") (pinfunction "LODRV1_29") (pintype "passive"))
      (node (ref "U9") (pin "4") (pinfunction "G_4") (pintype "passive"))
    )
    (net (code "25") (name "/LODRV2") (class "Default")
      (node (ref "U1") (pin "26") (pinfunction "LODRV2_26") (pintype "passive"))
      (node (ref "U8") (pin "4") (pinfunction "G_4") (pintype "passive"))
    )
    (net (code "26") (name "/LRCLK") (class "Default")
      (node (ref "U2") (pin "14") (pinfunction "LRCLK_14") (pintype "passive"))
    )
    (net (code "27") (name "/OR_Control") (class "Default")
      (node (ref "U5") (pin "3") (pinfunction "CTL_3") (pintype "input"))
    )
    (net (code "28") (name "/OTG{slash}VAP") (class "Default")
      (node (ref "U1") (pin "5") (pinfunction "OTG_VAP_5") (pintype "passive"))
    )
    (net (code "29") (name "/PROCHOT") (class "Default")
      (node (ref "U1") (pin "11") (pinfunction "PROCHOT_N_11") (pintype "passive"))
    )
    (net (code "30") (name "/Power Plug") (class "Default")
      (node (ref "C1") (pin "1") (pinfunction "1_1") (pintype "passive"))
      (node (ref "CR1") (pin "1") (pinfunction "1_1") (pintype "passive"))
      (node (ref "Q1") (pin "3") (pinfunction "3_3") (pintype "passive"))
    )
    (net (code "31") (name "/REGN") (class "Default")
      (node (ref "C7") (pin "2") (pinfunction "2_2") (pintype "passive"))
      (node (ref "R9") (pin "1") (pinfunction "1_1") (pintype "passive"))
      (node (ref "U1") (pin "28") (pinfunction "REGN_28") (pintype "passive"))
    )
    (net (code "32") (name "/SCL") (class "Default")
      (node (ref "U1") (pin "13") (pinfunction "SCL_13") (pintype "input"))
    )
    (net (code "35") (name "/SDA") (class "Default")
      (node (ref "U1") (pin "12") (pinfunction "SDA_12") (pintype "bidirectional"))
    )
    (net (code "37") (name "/SR_N") (class "Default")
      (node (ref "R27") (pin "2") (pinfunction "2_2") (pintype "passive"))
      (node (ref "U1") (pin "19") (pinfunction "SRN_19") (pintype "passive"))
    )
    (net (code "38") (name "/SR_P") (class "Default")
      (node (ref "R26") (pin "2") (pinfunction "2_2") (pintype "passive"))
      (node (ref "U1") (pin "20") (pinfunction "SRP_20") (pintype "passive"))
    )
    (net (code "40") (name "/SW1") (class "Default")
      (node (ref "C27") (pin "2") (pinfunction "2_2") (pintype "passive"))
      (node (ref "L3") (pin "2") (pinfunction "2_2") (pintype "passive"))
      (node (ref "U1") (pin "32") (pinfunction "SW1_32") (pintype "passive"))
      (node (ref "U6") (pin "1") (pinfunction "S_1") (pintype "passive"))
      (node (ref "U6") (pin "2") (pinfunction "S_2") (pintype "passive"))
      (node (ref "U6") (pin "3") (pinfunction "S_3") (pintype "passive"))
      (node (ref "U9") (pin "5") (pinfunction "D_5") (pintype "passive"))
      (node (ref "U9") (pin "6") (pinfunction "D_6") (pintype "passive"))
      (node (ref "U9") (pin "7") (pinfunction "D_7") (pintype "passive"))
      (node (ref "U9") (pin "8") (pinfunction "D_8") (pintype "passive"))
      (node (ref "U9") (pin "9") (pinfunction "D_9") (pintype "passive"))
    )
    (net (code "41") (name "/SW2") (class "Default")
      (node (ref "C28") (pin "2") (pinfunction "2_2") (pintype "passive"))
      (node (ref "L3") (pin "1") (pinfunction "1_1") (pintype "passive"))
      (node (ref "U1") (pin "23") (pinfunction "SW2_23") (pintype "passive"))
      (node (ref "U7") (pin "1") (pinfunction "S_1") (pintype "passive"))
      (node (ref "U7") (pin "2") (pinfunction "S_2") (pintype "passive"))
      (node (ref "U7") (pin "3") (pinfunction "S_3") (pintype "passive"))
      (node (ref "U8") (pin "5") (pinfunction "D_5") (pintype "passive"))
      (node (ref "U8") (pin "6") (pinfunction "D_6") (pintype "passive"))
      (node (ref "U8") (pin "7") (pinfunction "D_7") (pintype "passive"))
      (node (ref "U8") (pin "8") (pinfunction "D_8") (pintype "passive"))
      (node (ref "U8") (pin "9") (pinfunction "D_9") (pintype "passive"))
    )
    (net (code "45") (name "/VBAT") (class "Default")
      (node (ref "C25") (pin "1") (pinfunction "1_1") (pintype "passive"))
      (node (ref "C26") (pin "1") (pinfunction "1_1") (pintype "passive"))
      (node (ref "C43") (pin "1") (pinfunction "1_1") (pintype "passive"))
      (node (ref "Q2") (pin "2") (pinfunction "2_2") (pintype "passive"))
      (node (ref "R22") (pin "2") (pinfunction "2_2") (pintype "passive"))
      (node (ref "R27") (pin "1") (pinfunction "1_1") (pintype "passive"))
    )
    (net (code "46") (name "/VBUS") (class "Default")
      (node (ref "C29") (pin "1") (pinfunction "1_1") (pintype "passive"))
      (node (ref "C30") (pin "1") (pinfunction "1_1") (pintype "passive"))
      (node (ref "C31") (pin "1") (pinfunction "1_1") (pintype "passive"))
      (node (ref "C32") (pin "1") (pinfunction "1_1") (pintype "passive"))
      (node (ref "C33") (pin "1") (pinfunction "1_1") (pintype "passive"))
      (node (ref "C34") (pin "1") (pinfunction "1_1") (pintype "passive"))
      (node (ref "Q1") (pin "2") (pinfunction "2_2") (pintype "passive"))
      (node (ref "R21") (pin "1") (pinfunction "1_1") (pintype "passive"))
      (node (ref "R23") (pin "2") (pinfunction "2_2") (pintype "passive"))
      (node (ref "R24") (pin "1") (pinfunction "1_1") (pintype "passive"))
      (node (ref "U1") (pin "1") (pinfunction "VBUS_1") (pintype "power_in"))
      (node (ref "U5") (pin "6") (pinfunction "SENSE_6") (pintype "input"))
    )
    (net (code "47") (name "/VDDA") (class "Default")
      (node (ref "C9") (pin "1") (pinfunction "1_1") (pintype "passive"))
      (node (ref "R13") (pin "1") (pinfunction "1_1") (pintype "passive"))
      (node (ref "R2") (pin "1") (pinfunction "1_1") (pintype "passive"))
      (node (ref "R9") (pin "2") (pinfunction "2_2") (pintype "passive"))
      (node (ref "U1") (pin "7") (pinfunction "VDDA_7") (pintype "power_in"))
    )
    (net (code "48") (name "3V3") (class "Default")
      (node (ref "C13") (pin "1") (pinfunction "1_1") (pintype "passive"))
      (node (ref "R4") (pin "1") (pinfunction "1_1") (pintype "passive"))
      (node (ref "U2") (pin "4") (pinfunction "*SD_MODE_4") (pintype "passive"))
      (node (ref "U2") (pin "7") (pinfunction "VDD_7") (pintype "power_in"))
      (node (ref "U2") (pin "8") (pinfunction "VDD_8") (pintype "power_in"))
      (node (ref "U4") (pin "3") (pinfunction "Q_3") (pintype "power_in"))
    )
    (net (code "49") (name "5V") (class "Default")
      (node (ref "C12") (pin "1") (pinfunction "1_1") (pintype "passive"))
      (node (ref "C14") (pin "1") (pinfunction "1_1") (pintype "passive"))
      (node (ref "C16") (pin "1") (pinfunction "1_1") (pintype "passive"))
      (node (ref "C17") (pin "1") (pinfunction "1_1") (pintype "passive"))
      (node (ref "L2") (pin "1") (pinfunction "1_1") (pintype "passive"))
      (node (ref "U3") (pin "5") (pinfunction "FB_5") (pintype "passive"))
      (node (ref "U4") (pin "1") (pinfunction "I_1") (pintype "power_in"))
    )
    (net (code "50") (name "GND") (class "Default")
      (node (ref "C10") (pin "2") (pinfunction "2_2") (pintype "passive"))
      (node (ref "C12") (pin "2") (pinfunction "2_2") (pintype "passive"))
      (node (ref "C13") (pin "2") (pinfunction "2_2") (pintype "passive"))
      (node (ref "C14") (pin "2") (pinfunction "2_2") (pintype "passive"))
      (node (ref "C15") (pin "2") (pinfunction "2_2") (pintype "passive"))
      (node (ref "C16") (pin "2") (pinfunction "2_2") (pintype "passive"))
      (node (ref "C17") (pin "2") (pinfunction "2_2") (pintype "passive"))
      (node (ref "C18") (pin "2") (pinfunction "2_2") (pintype "passive"))
      (node (ref "C19") (pin "1") (pinfunction "C_1") (pintype "passive"))
      (node (ref "C20") (pin "1") (pinfunction "C_1") (pintype "passive"))
      (node (ref "C22") (pin "2") (pinfunction "2_2") (pintype "passive"))
      (node (ref "C24") (pin "2") (pinfunction "2_2") (pintype "passive"))
      (node (ref "C25") (pin "2") (pinfunction "2_2") (pintype "passive"))
      (node (ref "C26") (pin "2") (pinfunction "2_2") (pintype "passive"))
      (node (ref "C29") (pin "2") (pinfunction "2_2") (pintype "passive"))
      (node (ref "C3") (pin "2") (pinfunction "2_2") (pintype "passive"))
      (node (ref "C30") (pin "2") (pinfunction "2_2") (pintype "passive"))
      (node (ref "C31") (pin "2") (pinfunction "2_2") (pintype "passive"))
      (node (ref "C32") (pin "2") (pinfunction "2_2") (pintype "passive"))
      (node (ref "C33") (pin "2") (pinfunction "2_2") (pintype "passive"))
      (node (ref "C34") (pin "2") (pinfunction "2_2") (pintype "passive"))
      (node (ref "C35") (pin "2") (pinfunction "2_2") (pintype "passive"))
      (node (ref "C36") (pin "2") (pinfunction "2_2") (pintype "passive"))
      (node (ref "C37") (pin "2") (pinfunction "2_2") (pintype "passive"))
      (node (ref "C38") (pin "2") (pinfunction "2_2") (pintype "passive"))
      (node (ref "C39") (pin "2") (pinfunction "2_2") (pintype "passive"))
      (node (ref "C4") (pin "2") (pinfunction "2_2") (pintype "passive"))
      (node (ref "C40") (pin "2") (pinfunction "2_2") (pintype "passive"))
      (node (ref "C41") (pin "2") (pinfunction "2_2") (pintype "passive"))
      (node (ref "C42") (pin "2") (pinfunction "2_2") (pintype "passive"))
      (node (ref "C44") (pin "2") (pinfunction "2_2") (pintype "passive"))
      (node (ref "C45") (pin "2") (pinfunction "2_2") (pintype "passive"))
      (node (ref "C46") (pin "2") (pinfunction "2_2") (pintype "passive"))
      (node (ref "C47") (pin "1") (pinfunction "1_1") (pintype "passive"))
      (node (ref "C5") (pin "2") (pinfunction "2_2") (pintype "passive"))
      (node (ref "C6") (pin "2") (pinfunction "2_2") (pintype "passive"))
      (node (ref "C7") (pin "1") (pinfunction "1_1") (pintype "passive"))
      (node (ref "C8") (pin "2") (pinfunction "2_2") (pintype "passive"))
      (node (ref "C9") (pin "2") (pinfunction "2_2") (pintype "passive"))
      (node (ref "CR1") (pin "2") (pinfunction "2_2") (pintype "passive"))
      (node (ref "Q4") (pin "3") (pinfunction "3_3") (pintype "passive"))
      (node (ref "R14") (pin "2") (pinfunction "2_2") (pintype "passive"))
      (node (ref "R15") (pin "2") (pinfunction "2_2") (pintype "passive"))
      (node (ref "R16") (pin "2") (pinfunction "2_2") (pintype "passive"))
      (node (ref "R17") (pin "1") (pinfunction "1_1") (pintype "passive"))
      (node (ref "R17") (pin "3") (pinfunction "MNT_1_3") (pintype "passive"))
      (node (ref "R18") (pin "3") (pinfunction "MNT_1_3") (pintype "passive"))
      (node (ref "R3") (pin "2") (pinfunction "2_2") (pintype "passive"))
      (node (ref "U1") (pin "15") (pinfunction "CMPOUT_15") (pintype "passive"))
      (node (ref "U1") (pin "27") (pinfunction "PGND_27") (pintype "power_in"))
      (node (ref "U1") (pin "33") (pinfunction "Thermal_Pad_33") (pintype "passive"))
      (node (ref "U2") (pin "11") (pinfunction "GND_11") (pintype "power_in"))
      (node (ref "U2") (pin "15") (pinfunction "GND_15") (pintype "power_in"))
      (node (ref "U2") (pin "17") (pinfunction "EPAD_17") (pintype "passive"))
      (node (ref "U2") (pin "2") (pinfunction "GAIN_SLOT_2") (pintype "passive"))
      (node (ref "U2") (pin "3") (pinfunction "GND_3") (pintype "power_in"))
      (node (ref "U3") (pin "14") (pinfunction "PGND_14") (pintype "power_in"))
      (node (ref "U3") (pin "15") (pinfunction "PGND_15") (pintype "power_in"))
      (node (ref "U3") (pin "17") (pinfunction "PGND_PAD_17") (pintype "power_in"))
      (node (ref "U3") (pin "4") (pinfunction "GND_4") (pintype "power_in"))
      (node (ref "U4") (pin "2") (pinfunction "GND_2") (pintype "power_in"))
      (node (ref "U4") (pin "4") (pinfunction "GND_4") (pintype "power_in"))
      (node (ref "U5") (pin "2") (pinfunction "GND_2") (pintype "power_in"))
      (node (ref "U8") (pin "1") (pinfunction "S_1") (pintype "passive"))
      (node (ref "U8") (pin "2") (pinfunction "S_2") (pintype "passive"))
      (node (ref "U8") (pin "3") (pinfunction "S_3") (pintype "passive"))
      (node (ref "U9") (pin "1") (pinfunction "S_1") (pintype "passive"))
      (node (ref "U9") (pin "2") (pinfunction "S_2") (pintype "passive"))
      (node (ref "U9") (pin "3") (pinfunction "S_3") (pintype "passive"))
    )
    (net (code "51") (name "Net-(C4-Pad1)") (class "Default")
      (node (ref "C4") (pin "1") (pinfunction "1_1") (pintype "passive"))
      (node (ref "R6") (pin "2") (pinfunction "2_2") (pintype "passive"))
    )
    (net (code "52") (name "Net-(C5-Pad1)") (class "Default")
      (node (ref "C5") (pin "1") (pinfunction "1_1") (pintype "passive"))
      (node (ref "R7") (pin "2") (pinfunction "2_2") (pintype "passive"))
    )
    (net (code "53") (name "Net-(C11-Pad2)") (class "Default")
      (node (ref "C11") (pin "2") (pinfunction "2_2") (pintype "passive"))
      (node (ref "L2") (pin "2") (pinfunction "2_2") (pintype "passive"))
      (node (ref "U3") (pin "1") (pinfunction "VSW_1") (pintype "power_in"))
      (node (ref "U3") (pin "12") (pinfunction "VSW_12") (pintype "power_in"))
      (node (ref "U3") (pin "13") (pinfunction "VSW_13") (pintype "power_in"))
      (node (ref "U3") (pin "16") (pinfunction "VSW_16") (pintype "passive"))
    )
    (net (code "54") (name "Net-(C18-Pad1)") (class "Default")
      (node (ref "C18") (pin "1") (pinfunction "1_1") (pintype "passive"))
      (node (ref "C22") (pin "1") (pinfunction "1_1") (pintype "passive"))
      (node (ref "R21") (pin "2") (pinfunction "2_2") (pintype "passive"))
      (node (ref "R25") (pin "1") (pinfunction "1_1") (pintype "passive"))
      (node (ref "U6") (pin "5") (pinfunction "D_5") (pintype "passive"))
      (node (ref "U6") (pin "6") (pinfunction "D_6") (pintype "passive"))
      (node (ref "U6") (pin "7") (pinfunction "D_7") (pintype "passive"))
      (node (ref "U6") (pin "8") (pinfunction "D_8") (pintype "passive"))
      (node (ref "U6") (pin "9") (pinfunction "D_9") (pintype "passive"))
    )
    (net (code "55") (name "Net-(C43-Pad2)") (class "Default")
      (node (ref "C43") (pin "2") (pinfunction "2_2") (pintype "passive"))
      (node (ref "C47") (pin "2") (pinfunction "2_2") (pintype "passive"))
      (node (ref "F1") (pin "2") (pinfunction "2_2") (pintype "passive"))
      (node (ref "R22") (pin "1") (pinfunction "1_1") (pintype "passive"))
      (node (ref "R26") (pin "1") (pinfunction "1_1") (pintype "passive"))
    )
    (net (code "56") (name "Net-(C44-Pad1)") (class "Default")
      (node (ref "C44") (pin "1") (pinfunction "1_1") (pintype "passive"))
      (node (ref "R23") (pin "1") (pinfunction "1_1") (pintype "passive"))
    )
    (net (code "57") (name "Net-(Q3-D)") (class "Default")
      (node (ref "F1") (pin "1") (pinfunction "1_1") (pintype "passive"))
      (node (ref "Q3") (pin "5_8") (pinfunction "D_5_8") (pintype "passive"))
    )
    (net (code "58") (name "Net-(R17-Pad2)") (class "Default")
      (node (ref "R17") (pin "2") (pinfunction "2_2") (pintype "passive"))
      (node (ref "R18") (pin "1") (pinfunction "1_1") (pintype "passive"))
    )
    (net (code "59") (name "Net-(U1-COMP1)") (class "Default")
      (node (ref "C3") (pin "1") (pinfunction "1_1") (pintype "passive"))
      (node (ref "R6") (pin "1") (pinfunction "1_1") (pintype "passive"))
      (node (ref "U1") (pin "16") (pinfunction "COMP1_16") (pintype "passive"))
    )
    (net (code "60") (name "Net-(U1-COMP2)") (class "Default")
      (node (ref "C6") (pin "1") (pinfunction "1_1") (pintype "passive"))
      (node (ref "R7") (pin "1") (pinfunction "1_1") (pintype "passive"))
      (node (ref "U1") (pin "17") (pinfunction "COMP2_17") (pintype "passive"))
    )
    (net (code "61") (name "Net-(U1-IADPT)") (class "Default")
      (node (ref "C10") (pin "1") (pinfunction "1_1") (pintype "passive"))
      (node (ref "R15") (pin "1") (pinfunction "1_1") (pintype "passive"))
      (node (ref "U1") (pin "8") (pinfunction "IADPT_8") (pintype "passive"))
    )
    (net (code "62") (name "Net-(U1-IBAT)") (class "Default")
      (node (ref "C8") (pin "1") (pinfunction "1_1") (pintype "passive"))
      (node (ref "U1") (pin "9") (pinfunction "IBAT_9") (pintype "passive"))
    )
    (net (code "63") (name "Net-(U1-PSYS)") (class "Default")
      (node (ref "R14") (pin "1") (pinfunction "1_1") (pintype "passive"))
      (node (ref "U1") (pin "10") (pinfunction "PSYS_10") (pintype "passive"))
    )
    (net (code "64") (name "Net-(U2-OUTN)") (class "Default")
      (node (ref "J5") (pin "1") (pinfunction "1_1") (pintype "passive"))
      (node (ref "L1") (pin "1") (pinfunction "1_1") (pintype "passive"))
      (node (ref "U2") (pin "10") (pinfunction "OUTN_10") (pintype "output"))
    )
    (net (code "65") (name "Net-(U2-OUTP)") (class "Default")
      (node (ref "J5") (pin "2") (pinfunction "2_2") (pintype "passive"))
      (node (ref "L1") (pin "2") (pinfunction "2_2") (pintype "passive"))
      (node (ref "U2") (pin "9") (pinfunction "OUTP_9") (pintype "output"))
    )
    (net (code "66") (name "Net-(U3-BST)") (class "Default")
      (node (ref "C11") (pin "1") (pinfunction "1_1") (pintype "passive"))
      (node (ref "U3") (pin "10") (pinfunction "BST_10") (pintype "passive"))
    )
    (net (code "67") (name "Net-(U5-GATE)") (class "Default")
      (node (ref "Q1") (pin "1") (pinfunction "1_1") (pintype "passive"))
      (node (ref "U5") (pin "5") (pinfunction "GATE_5") (pintype "passive"))
    )
    (net (code "68") (name "Net-(U5-VIN)") (class "Default")
      (node (ref "C1") (pin "2") (pinfunction "2_2") (pintype "passive"))
      (node (ref "U5") (pin "1") (pinfunction "VIN_1") (pintype "input"))
    )
    (net (code "69") (name "VSYS") (class "Default")
      (node (ref "C15") (pin "1") (pinfunction "1_1") (pintype "passive"))
      (node (ref "C19") (pin "2") (pinfunction "A_2") (pintype "passive"))
      (node (ref "C20") (pin "2") (pinfunction "A_2") (pintype "passive"))
      (node (ref "C24") (pin "1") (pinfunction "1_1") (pintype "passive"))
      (node (ref "C35") (pin "1") (pinfunction "1_1") (pintype "passive"))
      (node (ref "C36") (pin "1") (pinfunction "1_1") (pintype "passive"))
      (node (ref "C37") (pin "1") (pinfunction "1_1") (pintype "passive"))
      (node (ref "C38") (pin "1") (pinfunction "1_1") (pintype "passive"))
      (node (ref "C39") (pin "1") (pinfunction "1_1") (pintype "passive"))
      (node (ref "C40") (pin "1") (pinfunction "1_1") (pintype "passive"))
      (node (ref "C41") (pin "1") (pinfunction "1_1") (pintype "passive"))
      (node (ref "C42") (pin "1") (pinfunction "1_1") (pintype "passive"))
      (node (ref "Q3") (pin "1") (pinfunction "S_1") (pintype "passive"))
      (node (ref "Q3") (pin "2") (pinfunction "S_2") (pintype "passive"))
      (node (ref "Q3") (pin "3") (pinfunction "S_3") (pintype "passive"))
      (node (ref "U1") (pin "22") (pinfunction "VSYS_22") (pintype "passive"))
      (node (ref "U3") (pin "11") (pinfunction "VCC_11") (pintype "power_in"))
      (node (ref "U3") (pin "2") (pinfunction "VCC_2") (pintype "power_in"))
      (node (ref "U3") (pin "3") (pinfunction "VCC_3") (pintype "power_in"))
      (node (ref "U7") (pin "5") (pinfunction "D_5") (pintype "passive"))
      (node (ref "U7") (pin "6") (pinfunction "D_6") (pintype "passive"))
      (node (ref "U7") (pin "7") (pinfunction "D_7") (pintype "passive"))
      (node (ref "U7") (pin "8") (pinfunction "D_8") (pintype "passive"))
      (node (ref "U7") (pin "9") (pinfunction "D_9") (pintype "passive"))
    )
    (net (code "70") (name "unconnected-(U1-CMPIN-Pad14)") (class "Default")
      (node (ref "U1") (pin "14") (pinfunction "CMPIN_14") (pintype "passive"))
    )
    (net (code "71") (name "unconnected-(U2-N.C.-Pad5)") (class "Default")
      (node (ref "U2") (pin "5") (pinfunction "N.C._5") (pintype "passive"))
    )
    (net (code "72") (name "unconnected-(U2-N.C.-Pad6)") (class "Default")
      (node (ref "U2") (pin "6") (pinfunction "N.C._6") (pintype "passive"))
    )
    (net (code "73") (name "unconnected-(U2-N.C.-Pad12)") (class "Default")
      (node (ref "U2") (pin "12") (pinfunction "N.C._12") (pintype "passive"))
    )
    (net (code "74") (name "unconnected-(U2-N.C.-Pad13)") (class "Default")
      (node (ref "U2") (pin "13") (pinfunction "N.C._13") (pintype "passive"))
    )
    (net (code "75") (name "unconnected-(U3-EN{slash}SYNC-Pad9)") (class "Default")
      (node (ref "U3") (pin "9") (pinfunction "EN/SYNC_9") (pintype "passive"))
    )
    (net (code "76") (name "unconnected-(U3-PG-Pad8)") (class "Default")
      (node (ref "U3") (pin "8") (pinfunction "PG_8") (pintype "passive"))
    )
    (net (code "77") (name "unconnected-(U5-STAT-Pad4)") (class "Default")
      (node (ref "U5") (pin "4") (pinfunction "STAT_4") (pintype "output"))
    )
  )
)
